# 10_PCIE2.net
KiCad netlist of a schematic drawn in Altium Designer
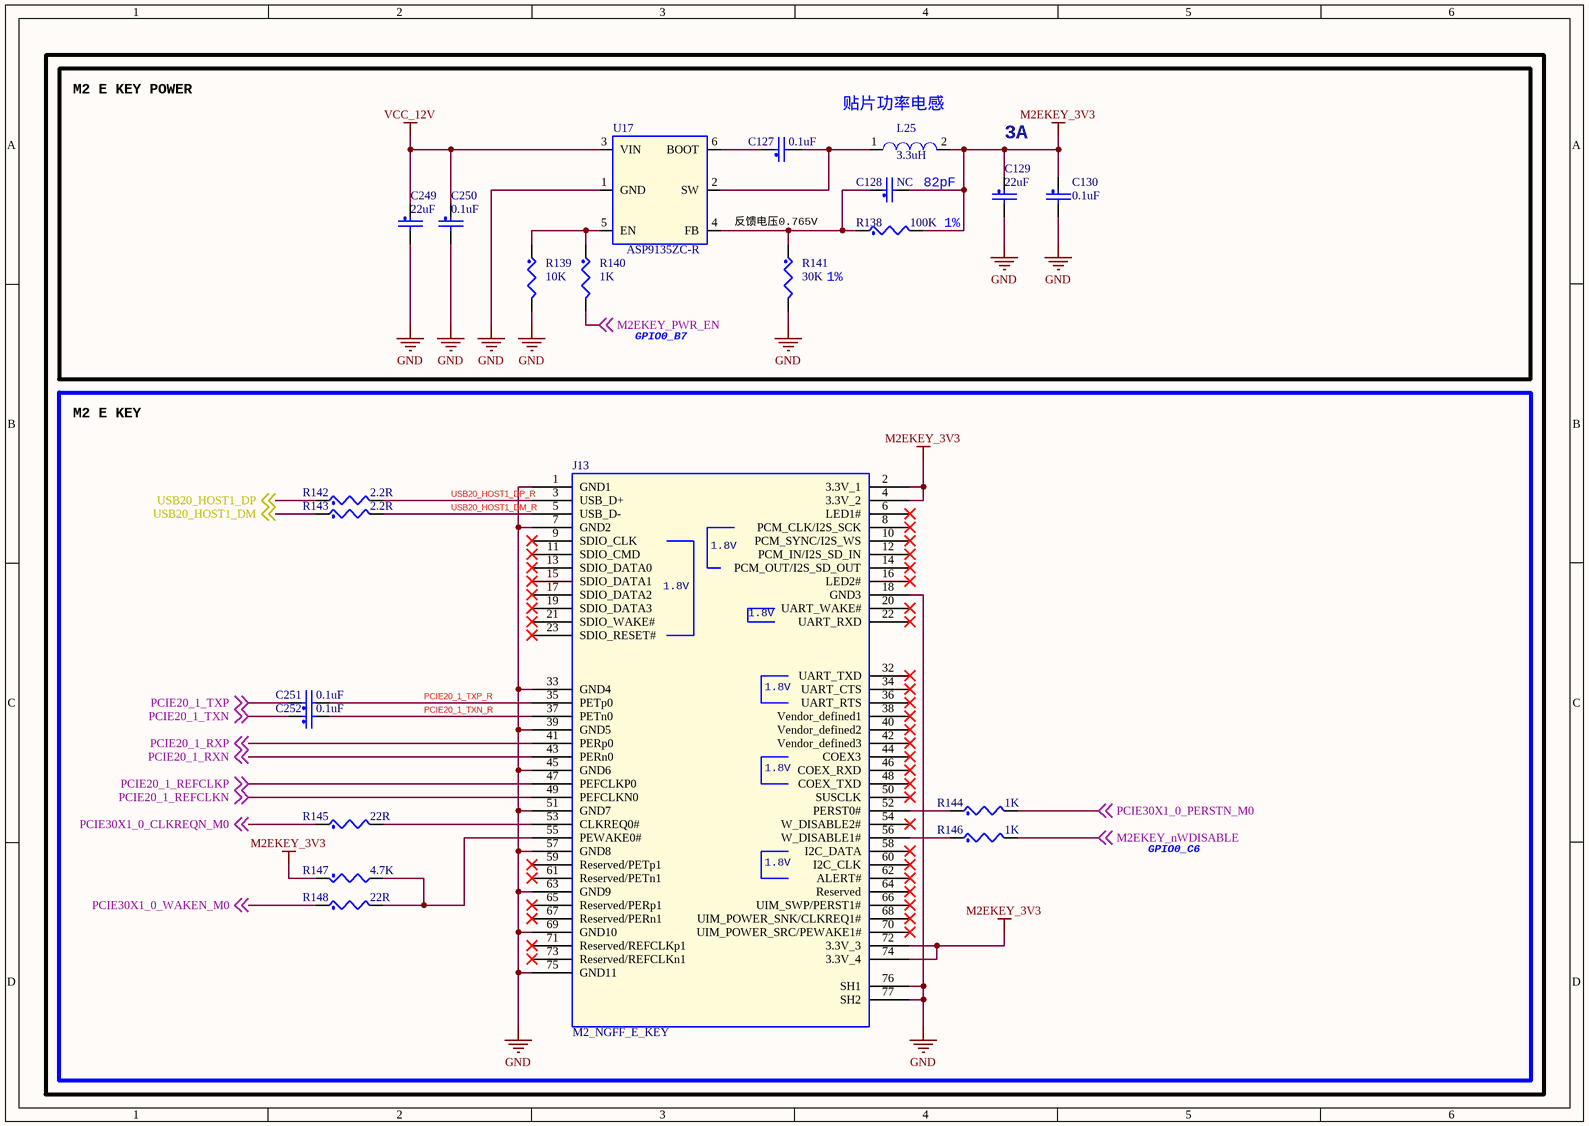
[diagram p0: 10.PCIE2.SchDoc]

(export (version "E")
  (design (tool "Eeschema 10.0.6"))
  (components
    (comp (ref "C127")
      (value "0.1uF")
      (footprint "0.PCB1:C0402")
      (libsource (lib "RK3588底板") (part "CAP_NP"))
    )
    (comp (ref "C128") (value "NC") (footprint "0.PCB1:C0402") (libsource (lib "RK3588底板") (part "CAP_NP")))
    (comp (ref "C129") (value "22uF") (footprint "0.PCB1:C0603") (libsource (lib "RK3588底板") (part "CAP_NP")))
    (comp (ref "C130")
      (value "0.1uF")
      (footprint "0.PCB1:C0402")
      (libsource (lib "RK3588底板") (part "CAP_NP"))
    )
    (comp (ref "C249") (value "22uF") (footprint "0.PCB1:C0603") (libsource (lib "RK3588底板") (part "CAP_NP")))
    (comp (ref "C250")
      (value "0.1uF")
      (footprint "0.PCB1:C0402")
      (libsource (lib "RK3588底板") (part "CAP_NP"))
    )
    (comp (ref "C251")
      (value "0.1uF")
      (footprint "0.PCB1:C0402")
      (libsource (lib "RK3588底板") (part "CAP_NP"))
    )
    (comp (ref "C252")
      (value "0.1uF")
      (footprint "0.PCB1:C0402")
      (libsource (lib "RK3588底板") (part "CAP_NP"))
    )
    (comp (ref "J13")
      (value "M2_NGFF_E_KEY")
      (footprint "0.PCB1:M2_NGFF_E_KEY")
      (libsource (lib "RK3588底板") (part "M2_NGFF_E_KEY"))
    )
    (comp (ref "L25") (value "3.3uH") (footprint "0.PCB1:l4520") (libsource (lib "RK3588底板") (part "IND")))
    (comp (ref "R138") (value "100K") (footprint "0.PCB1:R0402") (libsource (lib "RK3588底板") (part "RES")))
    (comp (ref "R139") (value "10K") (footprint "0.PCB1:R0402") (libsource (lib "RK3588底板") (part "RES")))
    (comp (ref "R140") (value "1K") (footprint "0.PCB1:R0402") (libsource (lib "RK3588底板") (part "RES")))
    (comp (ref "R141") (value "30K") (footprint "0.PCB1:R0402") (libsource (lib "RK3588底板") (part "RES")))
    (comp (ref "R142") (value "2.2R") (footprint "0.PCB1:R0402") (libsource (lib "RK3588底板") (part "RES")))
    (comp (ref "R143") (value "2.2R") (footprint "0.PCB1:R0402") (libsource (lib "RK3588底板") (part "RES")))
    (comp (ref "R144") (value "1K") (footprint "0.PCB1:R0402") (libsource (lib "RK3588底板") (part "RES")))
    (comp (ref "R145") (value "22R") (footprint "0.PCB1:R0402") (libsource (lib "RK3588底板") (part "RES")))
    (comp (ref "R146") (value "1K") (footprint "0.PCB1:R0402") (libsource (lib "RK3588底板") (part "RES")))
    (comp (ref "R147") (value "4.7K") (footprint "0.PCB1:R0402") (libsource (lib "RK3588底板") (part "RES")))
    (comp (ref "R148") (value "22R") (footprint "0.PCB1:R0402") (libsource (lib "RK3588底板") (part "RES")))
    (comp (ref "U17")
      (value "ASP9135ZC-R")
      (footprint "0.PCB1:SOT23_6")
      (libsource (lib "RK3588底板") (part "TP6327GS6"))
    )
  )
  (nets
    (net (code "1") (name "/PCIE20_1_TXN_R") (class "Default")
      (node (ref "C252") (pin "2") (pinfunction "2_2") (pintype "passive"))
      (node (ref "J13") (pin "37") (pinfunction "PETn0_37") (pintype "passive"))
    )
    (net (code "2") (name "/PCIE20_1_TXP_R") (class "Default")
      (node (ref "C251") (pin "2") (pinfunction "2_2") (pintype "passive"))
      (node (ref "J13") (pin "35") (pinfunction "PETp0_35") (pintype "passive"))
    )
    (net (code "3") (name "/USB20_HOST1_DM_R") (class "Default")
      (node (ref "J13") (pin "5") (pinfunction "USB_D-_5") (pintype "passive"))
      (node (ref "R143") (pin "2") (pinfunction "2_2") (pintype "passive"))
    )
    (net (code "4") (name "/USB20_HOST1_DP_R") (class "Default")
      (node (ref "J13") (pin "3") (pinfunction "USB_D+_3") (pintype "passive"))
      (node (ref "R142") (pin "2") (pinfunction "2_2") (pintype "passive"))
    )
    (net (code "5") (name "GND") (class "Default")
      (node (ref "C129") (pin "2") (pinfunction "2_2") (pintype "passive"))
      (node (ref "C130") (pin "2") (pinfunction "2_2") (pintype "passive"))
      (node (ref "C249") (pin "2") (pinfunction "2_2") (pintype "passive"))
      (node (ref "C250") (pin "2") (pinfunction "2_2") (pintype "passive"))
      (node (ref "J13") (pin "1") (pinfunction "GND1_1") (pintype "passive"))
      (node (ref "J13") (pin "18") (pinfunction "GND3_18") (pintype "passive"))
      (node (ref "J13") (pin "33") (pinfunction "GND4_33") (pintype "passive"))
      (node (ref "J13") (pin "39") (pinfunction "GND5_39") (pintype "passive"))
      (node (ref "J13") (pin "45") (pinfunction "GND6_45") (pintype "passive"))
      (node (ref "J13") (pin "51") (pinfunction "GND7_51") (pintype "passive"))
      (node (ref "J13") (pin "57") (pinfunction "GND8_57") (pintype "passive"))
      (node (ref "J13") (pin "63") (pinfunction "GND9_63") (pintype "passive"))
      (node (ref "J13") (pin "69") (pinfunction "GND10_69") (pintype "passive"))
      (node (ref "J13") (pin "7") (pinfunction "GND2_7") (pintype "passive"))
      (node (ref "J13") (pin "75") (pinfunction "GND11_75") (pintype "passive"))
      (node (ref "J13") (pin "76") (pinfunction "SH1_76") (pintype "passive"))
      (node (ref "J13") (pin "77") (pinfunction "SH2_77") (pintype "passive"))
      (node (ref "R139") (pin "2") (pinfunction "2_2") (pintype "passive"))
      (node (ref "R141") (pin "2") (pinfunction "2_2") (pintype "passive"))
      (node (ref "U17") (pin "1") (pinfunction "GND_1") (pintype "passive"))
    )
    (net (code "6") (name "M2EKEY_3V3") (class "Default")
      (node (ref "C128") (pin "2") (pinfunction "2_2") (pintype "passive"))
      (node (ref "C129") (pin "1") (pinfunction "1_1") (pintype "passive"))
      (node (ref "C130") (pin "1") (pinfunction "1_1") (pintype "passive"))
      (node (ref "J13") (pin "2") (pinfunction "3.3V_1_2") (pintype "passive"))
      (node (ref "J13") (pin "4") (pinfunction "3.3V_2_4") (pintype "passive"))
      (node (ref "J13") (pin "72") (pinfunction "3.3V_3_72") (pintype "passive"))
      (node (ref "J13") (pin "74") (pinfunction "3.3V_4_74") (pintype "passive"))
      (node (ref "L25") (pin "2") (pinfunction "2_2") (pintype "passive"))
      (node (ref "R138") (pin "2") (pinfunction "2_2") (pintype "passive"))
      (node (ref "R147") (pin "1") (pinfunction "1_1") (pintype "passive"))
    )
    (net (code "7") (name "M2EKEY_PWR_EN") (class "Default")
      (node (ref "R140") (pin "2") (pinfunction "2_2") (pintype "passive"))
    )
    (net (code "8") (name "M2EKEY_nWDISABLE") (class "Default")
      (node (ref "R146") (pin "2") (pinfunction "2_2") (pintype "passive"))
    )
    (net (code "9") (name "Net-(J13-CLKREQ0#)") (class "Default")
      (node (ref "J13") (pin "53") (pinfunction "CLKREQ0#_53") (pintype "passive"))
      (node (ref "R145") (pin "2") (pinfunction "2_2") (pintype "passive"))
    )
    (net (code "10") (name "Net-(J13-PERST0#)") (class "Default")
      (node (ref "J13") (pin "52") (pinfunction "PERST0#_52") (pintype "passive"))
      (node (ref "R144") (pin "1") (pinfunction "1_1") (pintype "passive"))
    )
    (net (code "11") (name "Net-(J13-PEWAKE0#)") (class "Default")
      (node (ref "J13") (pin "55") (pinfunction "PEWAKE0#_55") (pintype "passive"))
      (node (ref "R147") (pin "2") (pinfunction "2_2") (pintype "passive"))
      (node (ref "R148") (pin "2") (pinfunction "2_2") (pintype "passive"))
    )
    (net (code "12") (name "Net-(J13-W_DISABLE1#)") (class "Default")
      (node (ref "J13") (pin "56") (pinfunction "W_DISABLE1#_56") (pintype "passive"))
      (node (ref "R146") (pin "1") (pinfunction "1_1") (pintype "passive"))
    )
    (net (code "13") (name "Net-(U17-BOOT)") (class "Default")
      (node (ref "C127") (pin "1") (pinfunction "1_1") (pintype "passive"))
      (node (ref "U17") (pin "6") (pinfunction "BOOT_6") (pintype "passive"))
    )
    (net (code "14") (name "Net-(U17-EN)") (class "Default")
      (node (ref "R139") (pin "1") (pinfunction "1_1") (pintype "passive"))
      (node (ref "R140") (pin "1") (pinfunction "1_1") (pintype "passive"))
      (node (ref "U17") (pin "5") (pinfunction "EN_5") (pintype "passive"))
    )
    (net (code "15") (name "Net-(U17-FB)") (class "Default")
      (node (ref "C128") (pin "1") (pinfunction "1_1") (pintype "passive"))
      (node (ref "R138") (pin "1") (pinfunction "1_1") (pintype "passive"))
      (node (ref "R141") (pin "1") (pinfunction "1_1") (pintype "passive"))
      (node (ref "U17") (pin "4") (pinfunction "FB_4") (pintype "passive"))
    )
    (net (code "16") (name "Net-(U17-SW)") (class "Default")
      (node (ref "C127") (pin "2") (pinfunction "2_2") (pintype "passive"))
      (node (ref "L25") (pin "1") (pinfunction "1_1") (pintype "passive"))
      (node (ref "U17") (pin "2") (pinfunction "SW_2") (pintype "passive"))
    )
    (net (code "17") (name "PCIE20_1_REFCLKN") (class "Default")
      (node (ref "J13") (pin "49") (pinfunction "PEFCLKN0_49") (pintype "passive"))
    )
    (net (code "18") (name "PCIE20_1_REFCLKP") (class "Default")
      (node (ref "J13") (pin "47") (pinfunction "PEFCLKP0_47") (pintype "passive"))
    )
    (net (code "19") (name "PCIE20_1_RXN") (class "Default")
      (node (ref "J13") (pin "43") (pinfunction "PERn0_43") (pintype "passive"))
    )
    (net (code "20") (name "PCIE20_1_RXP") (class "Default")
      (node (ref "J13") (pin "41") (pinfunction "PERp0_41") (pintype "passive"))
    )
    (net (code "21") (name "PCIE20_1_TXN") (class "Default")
      (node (ref "C252") (pin "1") (pinfunction "1_1") (pintype "passive"))
    )
    (net (code "22") (name "PCIE20_1_TXP") (class "Default")
      (node (ref "C251") (pin "1") (pinfunction "1_1") (pintype "passive"))
    )
    (net (code "23") (name "PCIE30X1_0_CLKREQN_M0") (class "Default")
      (node (ref "R145") (pin "1") (pinfunction "1_1") (pintype "passive"))
    )
    (net (code "24") (name "PCIE30X1_0_PERSTN_M0") (class "Default")
      (node (ref "R144") (pin "2") (pinfunction "2_2") (pintype "passive"))
    )
    (net (code "25") (name "PCIE30X1_0_WAKEN_M0") (class "Default")
      (node (ref "R148") (pin "1") (pinfunction "1_1") (pintype "passive"))
    )
    (net (code "26") (name "USB20_HOST1_DM") (class "Default")
      (node (ref "R143") (pin "1") (pinfunction "1_1") (pintype "passive"))
    )
    (net (code "27") (name "USB20_HOST1_DP") (class "Default")
      (node (ref "R142") (pin "1") (pinfunction "1_1") (pintype "passive"))
    )
    (net (code "28") (name "VCC_12V") (class "Default")
      (node (ref "C249") (pin "1") (pinfunction "1_1") (pintype "passive"))
      (node (ref "C250") (pin "1") (pinfunction "1_1") (pintype "passive"))
      (node (ref "U17") (pin "3") (pinfunction "VIN_3") (pintype "passive"))
    )
    (net (code "29") (name "unconnected-(J13-ALERT#-Pad62)") (class "Default")
      (node (ref "J13") (pin "62") (pinfunction "ALERT#_62") (pintype "passive+no_connect"))
    )
    (net (code "30") (name "unconnected-(J13-COEX3-Pad44)") (class "Default")
      (node (ref "J13") (pin "44") (pinfunction "COEX3_44") (pintype "passive+no_connect"))
    )
    (net (code "31") (name "unconnected-(J13-COEX_RXD-Pad46)") (class "Default")
      (node (ref "J13") (pin "46") (pinfunction "COEX_RXD_46") (pintype "passive+no_connect"))
    )
    (net (code "32") (name "unconnected-(J13-COEX_TXD-Pad48)") (class "Default")
      (node (ref "J13") (pin "48") (pinfunction "COEX_TXD_48") (pintype "passive+no_connect"))
    )
    (net (code "33") (name "unconnected-(J13-I2C_CLK-Pad60)") (class "Default")
      (node (ref "J13") (pin "60") (pinfunction "I2C_CLK_60") (pintype "passive+no_connect"))
    )
    (net (code "34") (name "unconnected-(J13-I2C_DATA-Pad58)") (class "Default")
      (node (ref "J13") (pin "58") (pinfunction "I2C_DATA_58") (pintype "passive+no_connect"))
    )
    (net (code "35") (name "unconnected-(J13-LED1#-Pad6)") (class "Default")
      (node (ref "J13") (pin "6") (pinfunction "LED1#_6") (pintype "passive+no_connect"))
    )
    (net (code "36") (name "unconnected-(J13-LED2#-Pad16)") (class "Default")
      (node (ref "J13") (pin "16") (pinfunction "LED2#_16") (pintype "passive+no_connect"))
    )
    (net (code "37") (name "unconnected-(J13-PCM_CLK{slash}I2S_SCK-Pad8)") (class "Default")
      (node (ref "J13") (pin "8") (pinfunction "PCM_CLK/I2S_SCK_8") (pintype "passive+no_connect"))
    )
    (net (code "38") (name "unconnected-(J13-PCM_IN{slash}I2S_SD_IN-Pad12)") (class "Default")
      (node (ref "J13") (pin "12") (pinfunction "PCM_IN/I2S_SD_IN_12") (pintype "passive+no_connect"))
    )
    (net (code "39") (name "unconnected-(J13-PCM_OUT{slash}I2S_SD_OUT-Pad14)") (class "Default")
      (node (ref "J13") (pin "14") (pinfunction "PCM_OUT/I2S_SD_OUT_14") (pintype "passive+no_connect"))
    )
    (net (code "40") (name "unconnected-(J13-PCM_SYNC{slash}I2S_WS-Pad10)") (class "Default")
      (node (ref "J13") (pin "10") (pinfunction "PCM_SYNC/I2S_WS_10") (pintype "passive+no_connect"))
    )
    (net (code "41") (name "unconnected-(J13-Reserved-Pad64)") (class "Default")
      (node (ref "J13") (pin "64") (pinfunction "Reserved_64") (pintype "passive+no_connect"))
    )
    (net (code "42") (name "unconnected-(J13-Reserved{slash}PERn1-Pad67)") (class "Default")
      (node (ref "J13") (pin "67") (pinfunction "Reserved/PERn1_67") (pintype "passive+no_connect"))
    )
    (net (code "43") (name "unconnected-(J13-Reserved{slash}PERp1-Pad65)") (class "Default")
      (node (ref "J13") (pin "65") (pinfunction "Reserved/PERp1_65") (pintype "passive+no_connect"))
    )
    (net (code "44") (name "unconnected-(J13-Reserved{slash}PETn1-Pad61)") (class "Default")
      (node (ref "J13") (pin "61") (pinfunction "Reserved/PETn1_61") (pintype "passive+no_connect"))
    )
    (net (code "45") (name "unconnected-(J13-Reserved{slash}PETp1-Pad59)") (class "Default")
      (node (ref "J13") (pin "59") (pinfunction "Reserved/PETp1_59") (pintype "passive+no_connect"))
    )
    (net (code "46") (name "unconnected-(J13-Reserved{slash}REFCLKn1-Pad73)") (class "Default")
      (node (ref "J13") (pin "73") (pinfunction "Reserved/REFCLKn1_73") (pintype "passive+no_connect"))
    )
    (net (code "47") (name "unconnected-(J13-Reserved{slash}REFCLKp1-Pad71)") (class "Default")
      (node (ref "J13") (pin "71") (pinfunction "Reserved/REFCLKp1_71") (pintype "passive+no_connect"))
    )
    (net (code "48") (name "unconnected-(J13-SDIO_CLK-Pad9)") (class "Default")
      (node (ref "J13") (pin "9") (pinfunction "SDIO_CLK_9") (pintype "passive+no_connect"))
    )
    (net (code "49") (name "unconnected-(J13-SDIO_CMD-Pad11)") (class "Default")
      (node (ref "J13") (pin "11") (pinfunction "SDIO_CMD_11") (pintype "passive+no_connect"))
    )
    (net (code "50") (name "unconnected-(J13-SDIO_DATA0-Pad13)") (class "Default")
      (node (ref "J13") (pin "13") (pinfunction "SDIO_DATA0_13") (pintype "passive+no_connect"))
    )
    (net (code "51") (name "unconnected-(J13-SDIO_DATA1-Pad15)") (class "Default")
      (node (ref "J13") (pin "15") (pinfunction "SDIO_DATA1_15") (pintype "passive+no_connect"))
    )
    (net (code "52") (name "unconnected-(J13-SDIO_DATA2-Pad17)") (class "Default")
      (node (ref "J13") (pin "17") (pinfunction "SDIO_DATA2_17") (pintype "passive+no_connect"))
    )
    (net (code "53") (name "unconnected-(J13-SDIO_DATA3-Pad19)") (class "Default")
      (node (ref "J13") (pin "19") (pinfunction "SDIO_DATA3_19") (pintype "passive+no_connect"))
    )
    (net (code "54") (name "unconnected-(J13-SDIO_RESET#-Pad23)") (class "Default")
      (node (ref "J13") (pin "23") (pinfunction "SDIO_RESET#_23") (pintype "passive+no_connect"))
    )
    (net (code "55") (name "unconnected-(J13-SDIO_WAKE#-Pad21)") (class "Default")
      (node (ref "J13") (pin "21") (pinfunction "SDIO_WAKE#_21") (pintype "passive+no_connect"))
    )
    (net (code "56") (name "unconnected-(J13-SUSCLK-Pad50)") (class "Default")
      (node (ref "J13") (pin "50") (pinfunction "SUSCLK_50") (pintype "passive+no_connect"))
    )
    (net (code "57") (name "unconnected-(J13-UART_CTS-Pad34)") (class "Default")
      (node (ref "J13") (pin "34") (pinfunction "UART_CTS_34") (pintype "passive+no_connect"))
    )
    (net (code "58") (name "unconnected-(J13-UART_RTS-Pad36)") (class "Default")
      (node (ref "J13") (pin "36") (pinfunction "UART_RTS_36") (pintype "passive+no_connect"))
    )
    (net (code "59") (name "unconnected-(J13-UART_RXD-Pad22)") (class "Default")
      (node (ref "J13") (pin "22") (pinfunction "UART_RXD_22") (pintype "passive+no_connect"))
    )
    (net (code "60") (name "unconnected-(J13-UART_TXD-Pad32)") (class "Default")
      (node (ref "J13") (pin "32") (pinfunction "UART_TXD_32") (pintype "passive+no_connect"))
    )
    (net (code "61") (name "unconnected-(J13-UART_WAKE#-Pad20)") (class "Default")
      (node (ref "J13") (pin "20") (pinfunction "UART_WAKE#_20") (pintype "passive+no_connect"))
    )
    (net (code "62") (name "unconnected-(J13-UIM_POWER_SNK{slash}CLKREQ1#-Pad68)") (class "Default")
      (node (ref "J13") (pin "68") (pinfunction "UIM_POWER_SNK/CLKREQ1#_68") (pintype "passive+no_connect"))
    )
    (net (code "63") (name "unconnected-(J13-UIM_POWER_SRC{slash}PEWAKE1#-Pad70)") (class "Default")
      (node (ref "J13") (pin "70") (pinfunction "UIM_POWER_SRC/PEWAKE1#_70") (pintype "passive+no_connect"))
    )
    (net (code "64") (name "unconnected-(J13-UIM_SWP{slash}PERST1#-Pad66)") (class "Default")
      (node (ref "J13") (pin "66") (pinfunction "UIM_SWP/PERST1#_66") (pintype "passive+no_connect"))
    )
    (net (code "65") (name "unconnected-(J13-Vendor_defined1-Pad38)") (class "Default")
      (node (ref "J13") (pin "38") (pinfunction "Vendor_defined1_38") (pintype "passive+no_connect"))
    )
    (net (code "66") (name "unconnected-(J13-Vendor_defined2-Pad40)") (class "Default")
      (node (ref "J13") (pin "40") (pinfunction "Vendor_defined2_40") (pintype "passive+no_connect"))
    )
    (net (code "67") (name "unconnected-(J13-Vendor_defined3-Pad42)") (class "Default")
      (node (ref "J13") (pin "42") (pinfunction "Vendor_defined3_42") (pintype "passive+no_connect"))
    )
    (net (code "68") (name "unconnected-(J13-W_DISABLE2#-Pad54)") (class "Default")
      (node (ref "J13") (pin "54") (pinfunction "W_DISABLE2#_54") (pintype "passive+no_connect"))
    )
  )
)
